# KONNEKTING_HW1_1_Rev1.net
KiCad netlist of a schematic drawn in EAGLE
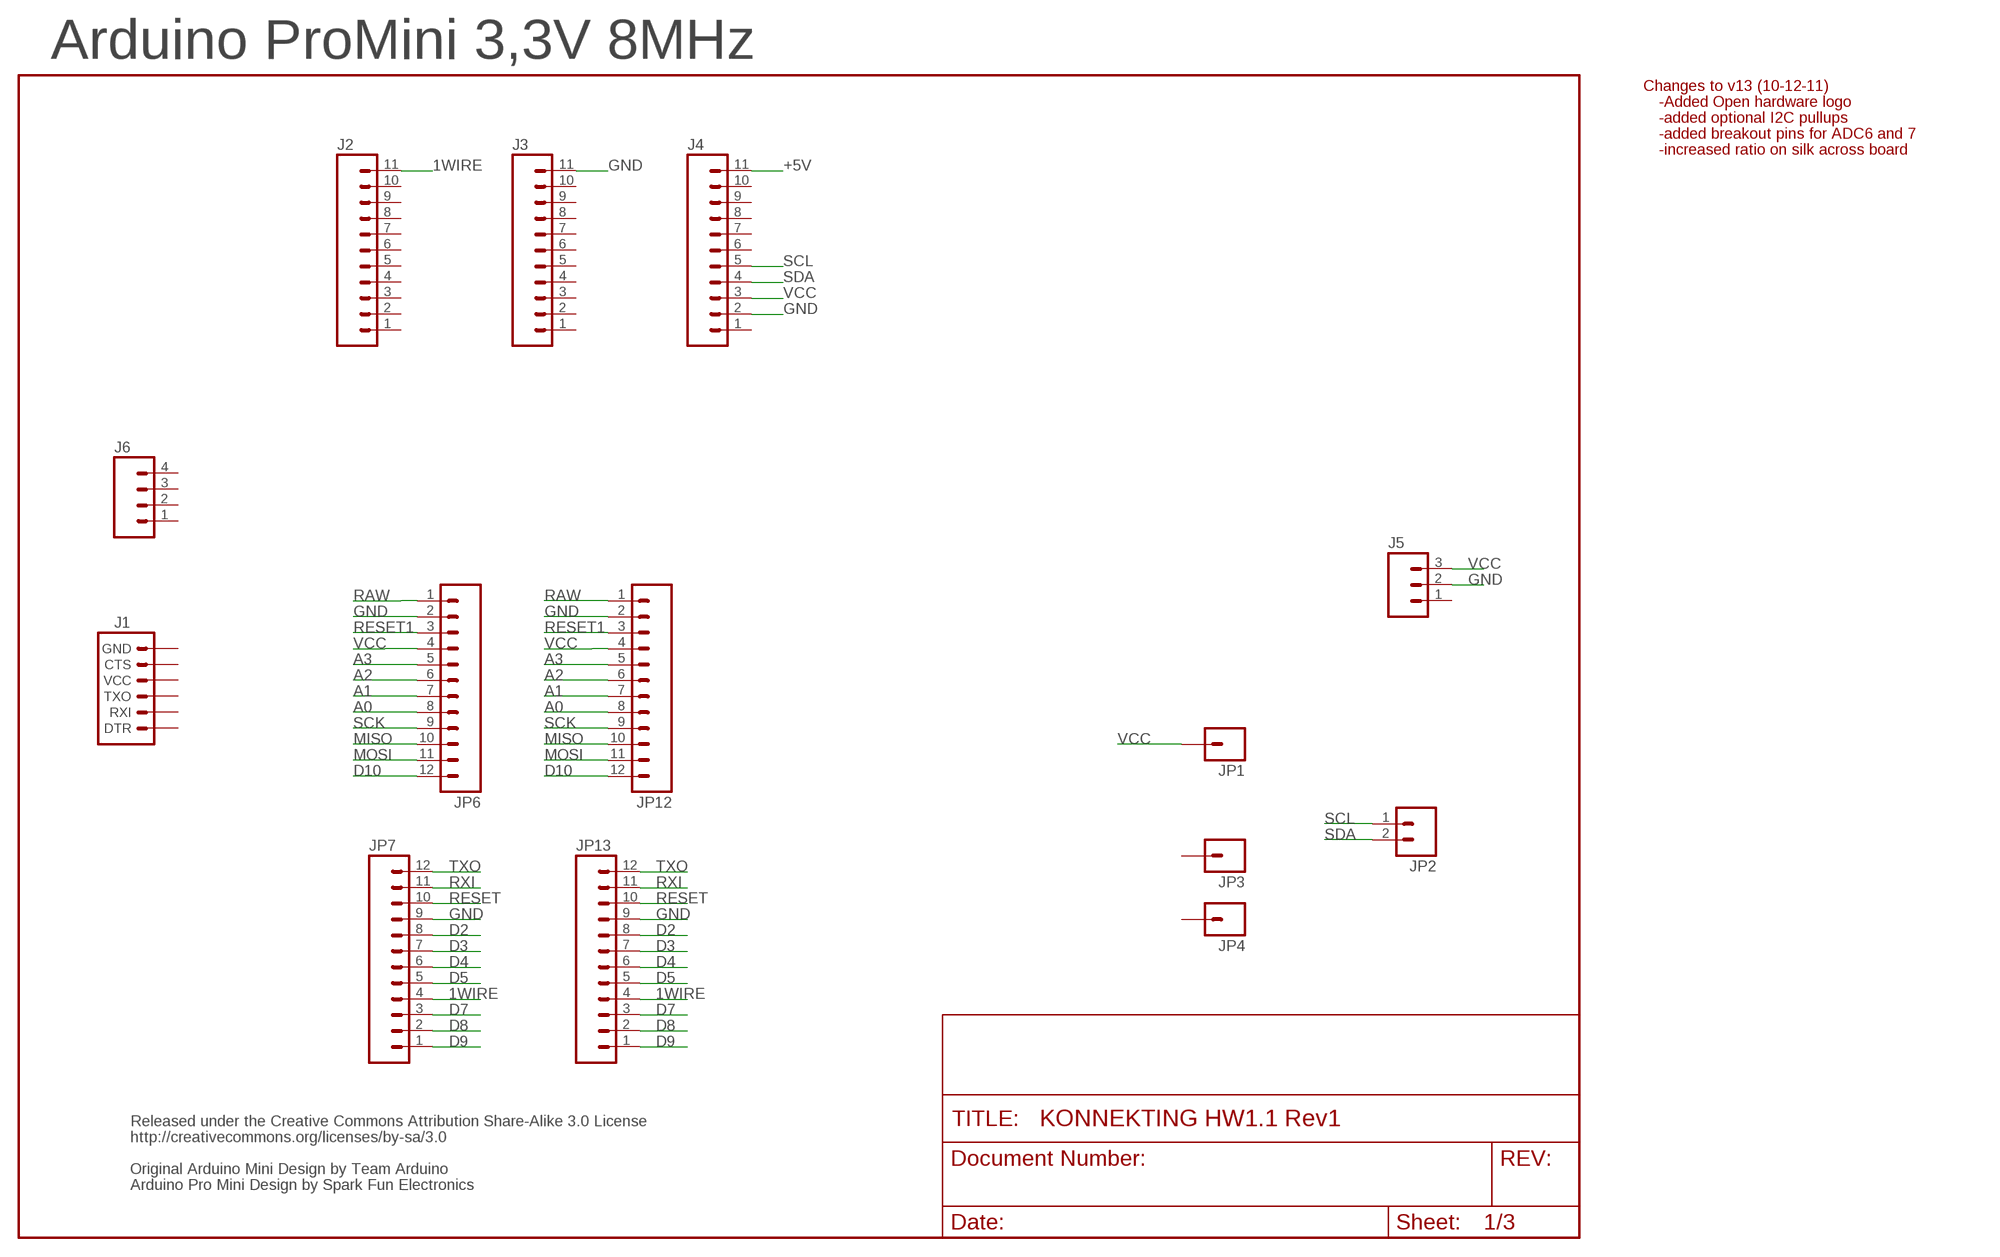
[diagram p0: schematic, sheet 1]
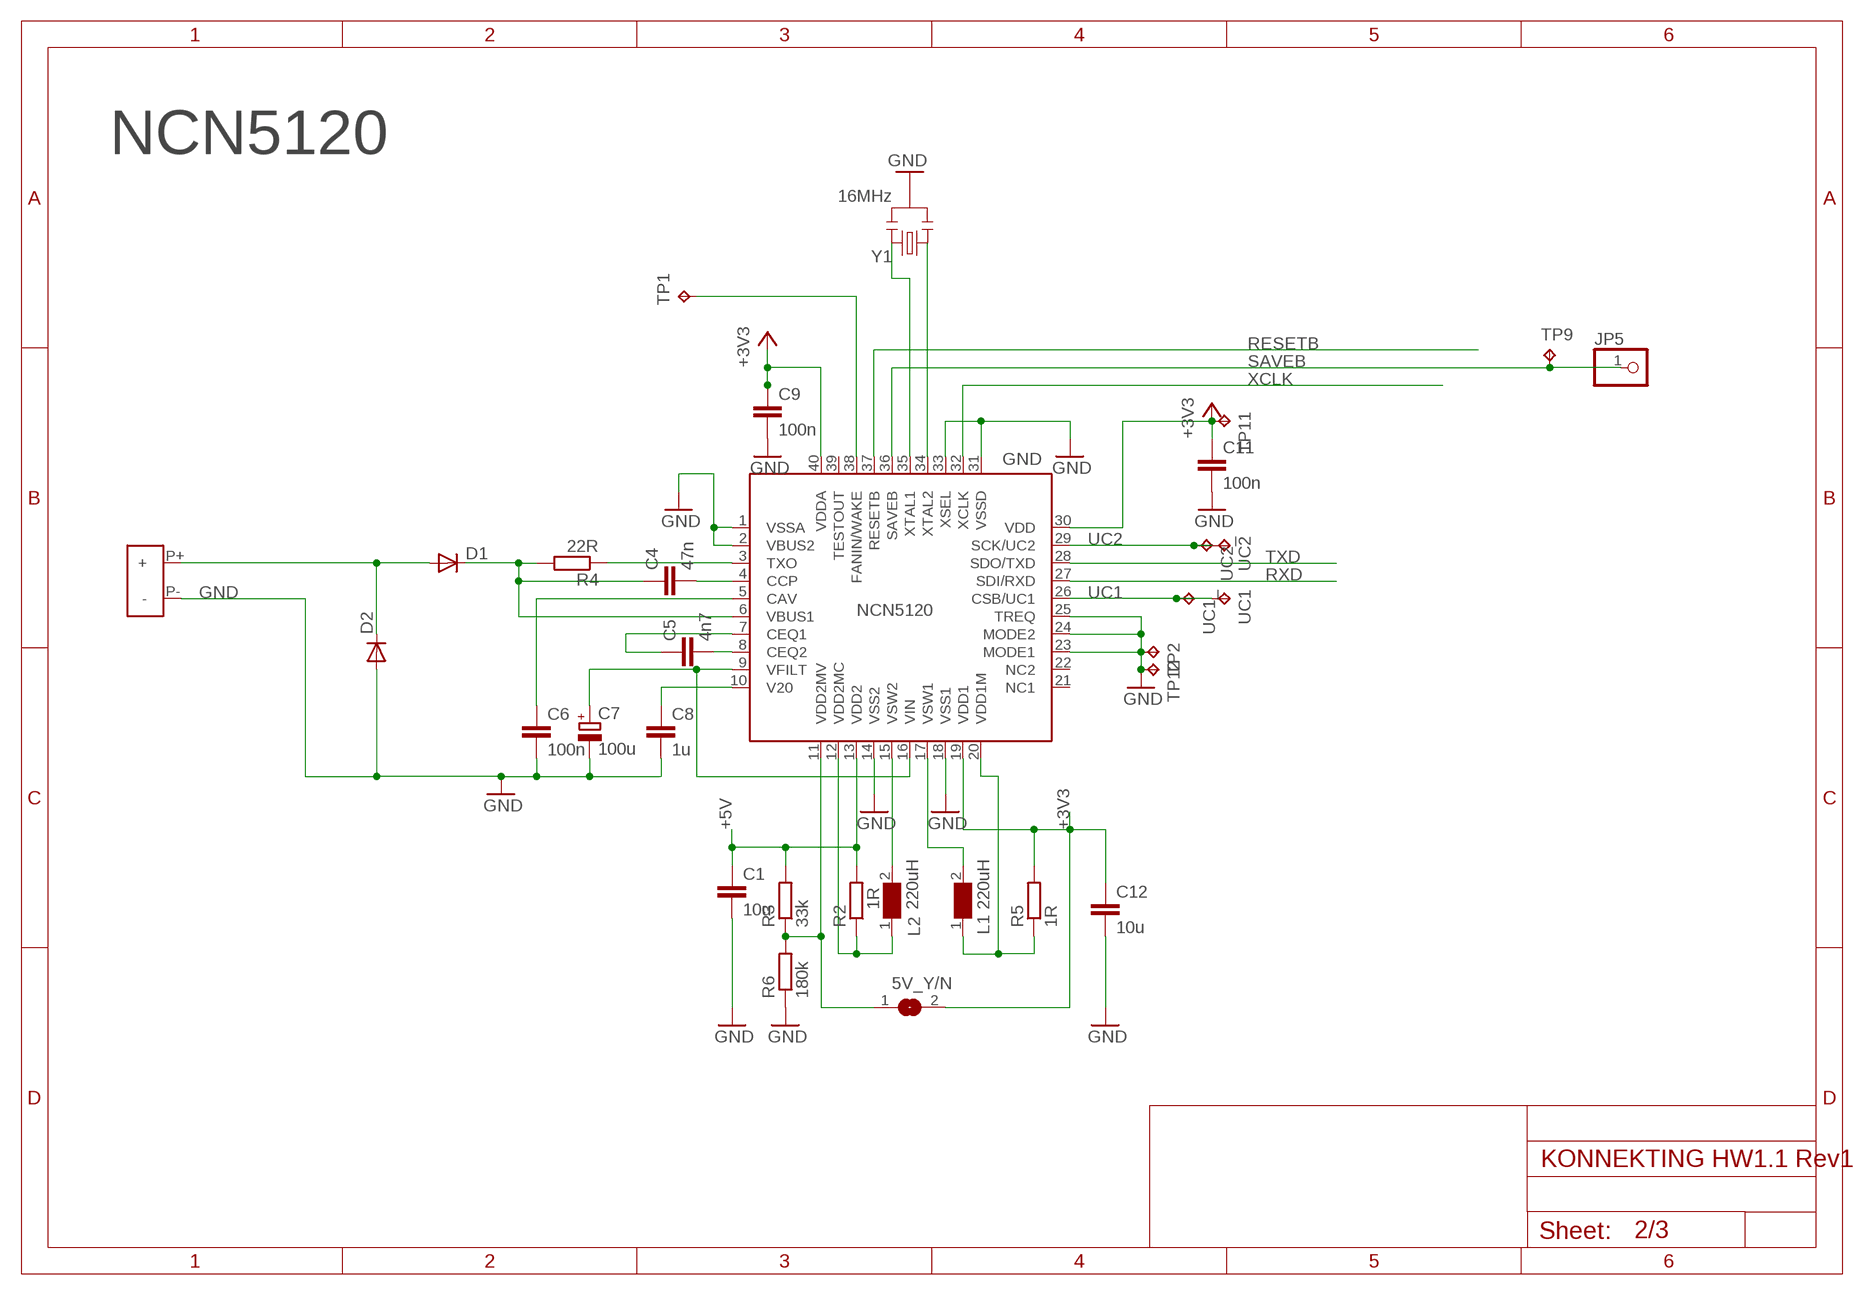
[diagram p1: schematic, sheet 2]
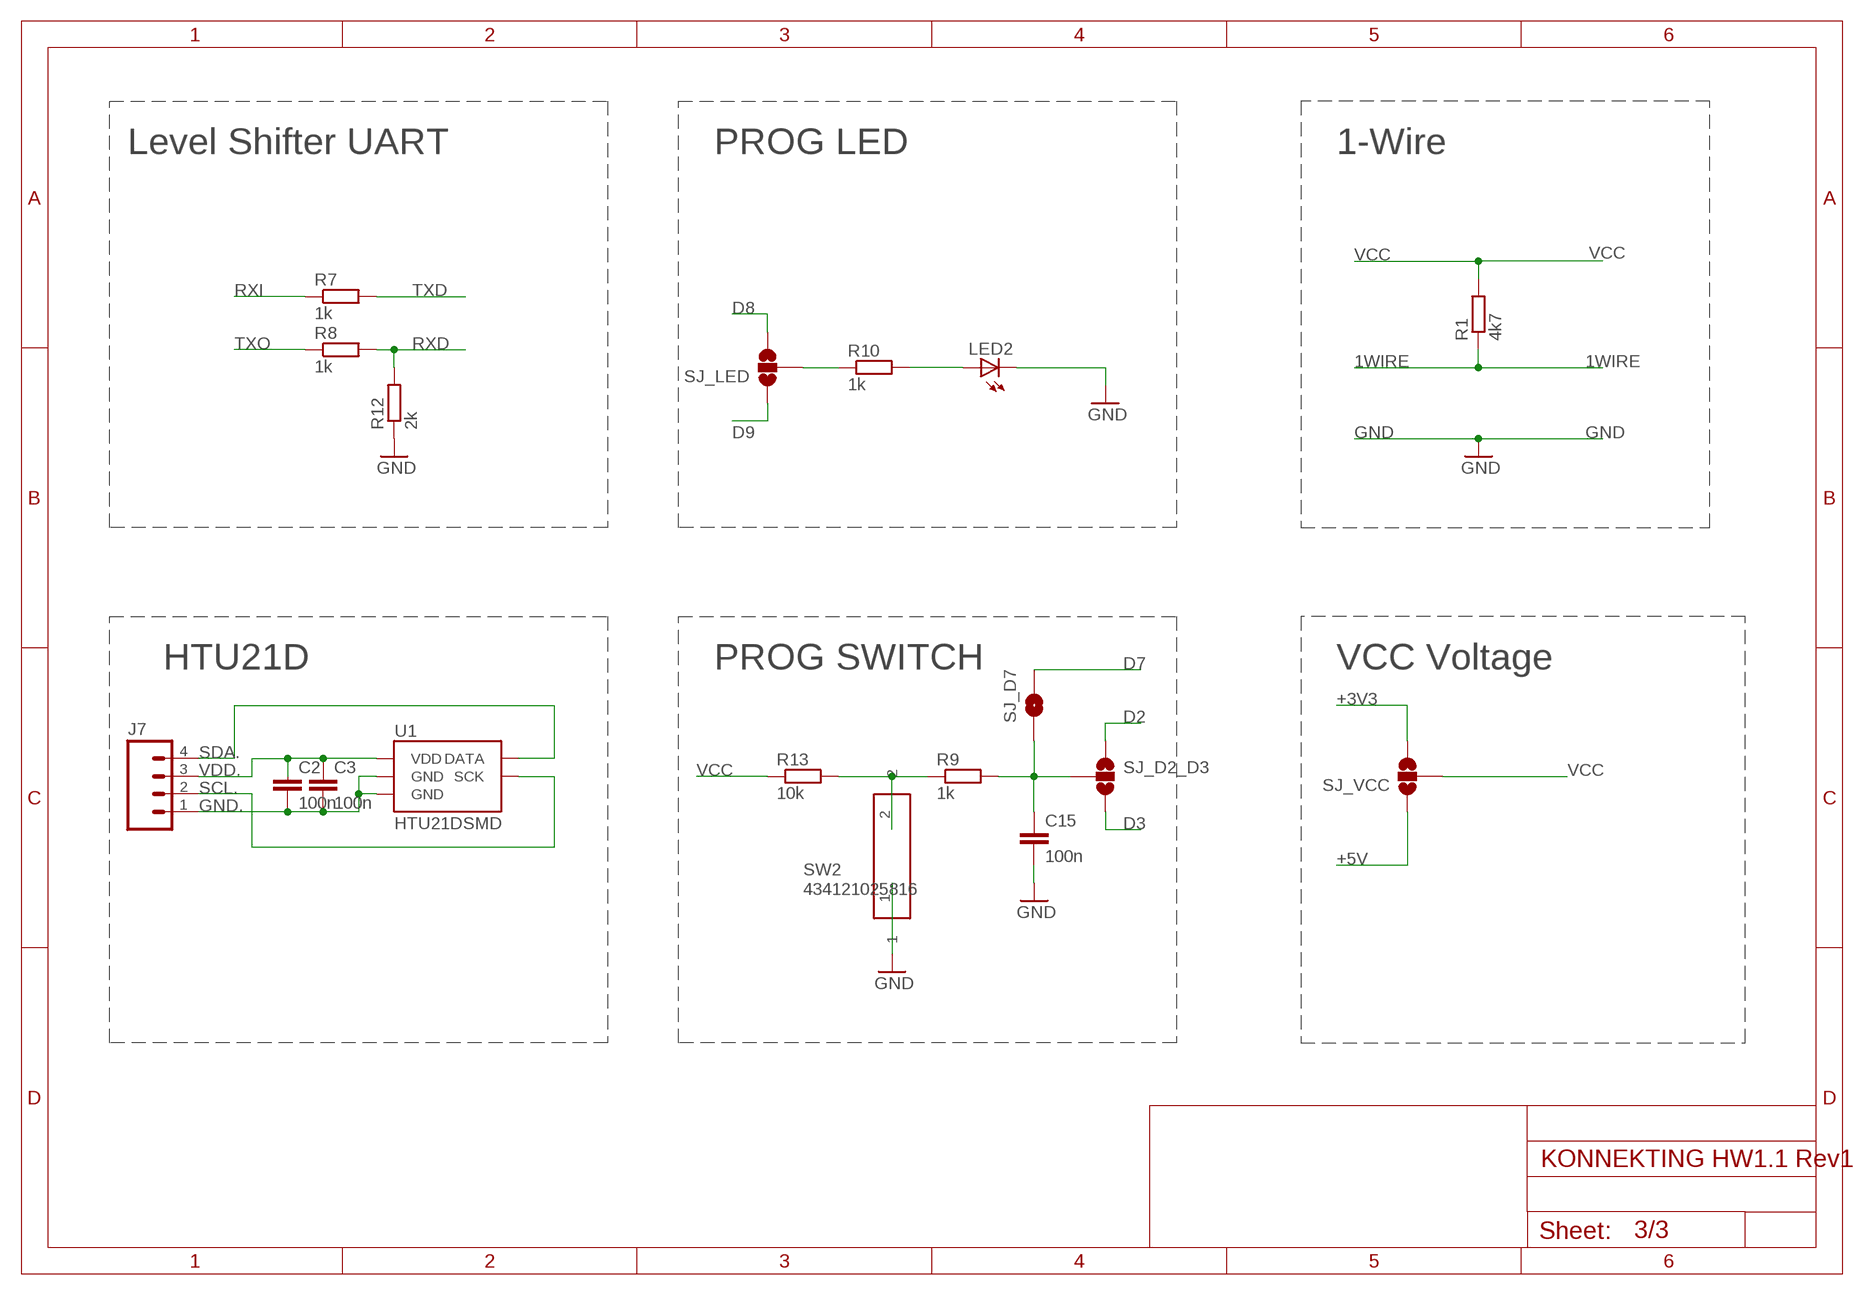
[diagram p2: schematic, sheet 3]

(export (version "E")
  (design (tool "Eeschema 10.0.6"))
  (components
    (comp (ref "J1")
      (value "ARDUINO_SERIAL_PROGRAMPTH")
      (footprint "eagle-import:1X06")
      (libsource (lib "eagle-import") (part "ARDUINO_SERIAL_PROGRAMPTH"))
    )
    (comp (ref "J2")
      (value "M11PTH")
      (footprint "eagle-import:1X11")
      (libsource (lib "eagle-import") (part "M11PTH"))
    )
    (comp (ref "J3")
      (value "M11PTH")
      (footprint "eagle-import:1X11")
      (libsource (lib "eagle-import") (part "M11PTH"))
    )
    (comp (ref "J4")
      (value "M11PTH")
      (footprint "eagle-import:1X11")
      (libsource (lib "eagle-import") (part "M11PTH"))
    )
    (comp (ref "J5")
      (value "M03PTH")
      (footprint "eagle-import:1X03")
      (libsource (lib "eagle-import") (part "M03PTH"))
    )
    (comp (ref "J6")
      (value "M04PTH")
      (footprint "eagle-import:1X04")
      (libsource (lib "eagle-import") (part "M04PTH"))
    )
    (comp (ref "JP1")
      (value "M01PTH")
      (footprint "eagle-import:1X01")
      (libsource (lib "eagle-import") (part "M01PTH"))
    )
    (comp (ref "JP2")
      (value "M02PTH")
      (footprint "eagle-import:1X02")
      (libsource (lib "eagle-import") (part "M02PTH"))
    )
    (comp (ref "JP3")
      (value "M01PTH")
      (footprint "eagle-import:1X01")
      (libsource (lib "eagle-import") (part "M01PTH"))
    )
    (comp (ref "JP4")
      (value "M01PTH")
      (footprint "eagle-import:1X01")
      (libsource (lib "eagle-import") (part "M01PTH"))
    )
    (comp (ref "JP6")
      (value "M12PTH")
      (footprint "eagle-import:1X12")
      (libsource (lib "eagle-import") (part "M12PTH"))
    )
    (comp (ref "JP7")
      (value "M12PTH")
      (footprint "eagle-import:1X12")
      (libsource (lib "eagle-import") (part "M12PTH"))
    )
    (comp (ref "JP12")
      (value "M12PTH")
      (footprint "eagle-import:1X12")
      (libsource (lib "eagle-import") (part "M12PTH"))
    )
    (comp (ref "JP13")
      (value "M12PTH")
      (footprint "eagle-import:1X12")
      (libsource (lib "eagle-import") (part "M12PTH"))
    )
    (comp (ref "5V_Y/N")
      (value "SJ")
      (footprint "eagle-import:SJ")
      (libsource (lib "eagle-import") (part "SJ"))
    )
    (comp (ref "C1")
      (value "10u")
      (footprint "eagle-import:C0805")
      (libsource (lib "eagle-import") (part "C-EUC0805"))
    )
    (comp (ref "C4")
      (value "47n")
      (footprint "eagle-import:C0603")
      (libsource (lib "eagle-import") (part "C-EUC0603"))
    )
    (comp (ref "C5")
      (value "4n7")
      (footprint "eagle-import:C0603")
      (libsource (lib "eagle-import") (part "C-EUC0603"))
    )
    (comp (ref "C6")
      (value "100n")
      (footprint "eagle-import:C0603")
      (libsource (lib "eagle-import") (part "C-EUC0603"))
    )
    (comp (ref "C7")
      (value "100u")
      (footprint "eagle-import:UD-6,3X7,7_NICHICON")
      (libsource (lib "eagle-import") (part "CPOL-EUUD-6,3X7,7"))
    )
    (comp (ref "C8")
      (value "1u")
      (footprint "eagle-import:C0603")
      (libsource (lib "eagle-import") (part "C-EUC0603"))
    )
    (comp (ref "C9")
      (value "100n")
      (footprint "eagle-import:C0603")
      (libsource (lib "eagle-import") (part "C-EUC0603"))
    )
    (comp (ref "C11")
      (value "100n")
      (footprint "eagle-import:C0603")
      (libsource (lib "eagle-import") (part "C-EUC0603"))
    )
    (comp (ref "C12")
      (value "10u")
      (footprint "eagle-import:C0805")
      (libsource (lib "eagle-import") (part "C-EUC0805"))
    )
    (comp (ref "D1")
      (value "DIODESMA-ALT")
      (footprint "eagle-import:SMA-DIODE_ALT")
      (libsource (lib "eagle-import") (part "DIODESMA-ALT"))
    )
    (comp (ref "D2")
      (value "DIODESMA-ALT")
      (footprint "eagle-import:SMA-DIODE_ALT")
      (libsource (lib "eagle-import") (part "DIODESMA-ALT"))
    )
    (comp (ref "GND")
      (value "NCN5120_KNX_TRANSCEIVER")
      (footprint "eagle-import:QFN40")
      (libsource (lib "eagle-import") (part "NCN5120_KNX_TRANSCEIVER"))
    )
    (comp (ref "JP5")
      (value "PINHD-1X1")
      (footprint "eagle-import:1X01")
      (libsource (lib "eagle-import") (part "PINHD-1X1"))
    )
    (comp (ref "L1")
      (value "220uH")
      (footprint "eagle-import:WE-PD2_7850")
      (libsource (lib "eagle-import") (part "WE-PD2_7850"))
    )
    (comp (ref "L2")
      (value "220uH")
      (footprint "eagle-import:WE-PD2_7850")
      (libsource (lib "eagle-import") (part "WE-PD2_7850"))
    )
    (comp (ref "R2")
      (value "1R")
      (footprint "eagle-import:R0603")
      (libsource (lib "eagle-import") (part "R-EU_R0603"))
    )
    (comp (ref "R3")
      (value "33k")
      (footprint "eagle-import:R0603")
      (libsource (lib "eagle-import") (part "R-EU_R0603"))
    )
    (comp (ref "R4")
      (value "22R")
      (footprint "eagle-import:R2512")
      (libsource (lib "eagle-import") (part "R-EU_R2512"))
    )
    (comp (ref "R5")
      (value "1R")
      (footprint "eagle-import:R0603")
      (libsource (lib "eagle-import") (part "R-EU_R0603"))
    )
    (comp (ref "R6")
      (value "180k")
      (footprint "eagle-import:R0603")
      (libsource (lib "eagle-import") (part "R-EU_R0603"))
    )
    (comp (ref "TP1")
      (value "TPTP10SQ")
      (footprint "eagle-import:TP10SQ")
      (libsource (lib "eagle-import") (part "TPTP10SQ"))
    )
    (comp (ref "TP2")
      (value "TPTP09SQ")
      (footprint "eagle-import:TP09SQ")
      (libsource (lib "eagle-import") (part "TPTP09SQ"))
    )
    (comp (ref "TP9")
      (value "TPTP10SQ")
      (footprint "eagle-import:TP10SQ")
      (libsource (lib "eagle-import") (part "TPTP10SQ"))
    )
    (comp (ref "TP11")
      (value "TPTP09SQ")
      (footprint "eagle-import:TP09SQ")
      (libsource (lib "eagle-import") (part "TPTP09SQ"))
    )
    (comp (ref "TP12")
      (value "TPTP09SQ")
      (footprint "eagle-import:TP09SQ")
      (libsource (lib "eagle-import") (part "TPTP09SQ"))
    )
    (comp (ref "U$2")
      (value "KNX_KLEMME")
      (footprint "eagle-import:KNX_KLEMME")
      (libsource (lib "eagle-import") (part "KNX_KLEMME"))
    )
    (comp (ref "UC1")
      (value "TPTP09SQ")
      (footprint "eagle-import:TP09SQ")
      (libsource (lib "eagle-import") (part "TPTP09SQ"))
    )
    (comp (ref "UC1_")
      (value "TPTP09SQ")
      (footprint "eagle-import:TP09SQ")
      (libsource (lib "eagle-import") (part "TPTP09SQ"))
    )
    (comp (ref "UC2")
      (value "TPTP09SQ")
      (footprint "eagle-import:TP09SQ")
      (libsource (lib "eagle-import") (part "TPTP09SQ"))
    )
    (comp (ref "UC2_")
      (value "TPTP09SQ")
      (footprint "eagle-import:TP09SQ")
      (libsource (lib "eagle-import") (part "TPTP09SQ"))
    )
    (comp (ref "Y1")
      (value "16MHz")
      (footprint "eagle-import:RESONATOR-SMD")
      (libsource (lib "eagle-import") (part "RESONATORSMD"))
    )
    (comp (ref "C2")
      (value "100n")
      (footprint "eagle-import:0603-CAP")
      (libsource (lib "eagle-import") (part "CAP0603-CAP"))
    )
    (comp (ref "C3")
      (value "100n")
      (footprint "eagle-import:0603-CAP")
      (libsource (lib "eagle-import") (part "CAP0603-CAP"))
    )
    (comp (ref "C15")
      (value "100n")
      (footprint "eagle-import:C0603")
      (libsource (lib "eagle-import") (part "C-EUC0603"))
    )
    (comp (ref "J7")
      (value "M04PTH")
      (footprint "eagle-import:1X04")
      (libsource (lib "eagle-import") (part "M04PTH"))
    )
    (comp (ref "LED2")
      (value "LEDCHIP-LED0805")
      (footprint "eagle-import:CHIP-LED0805")
      (libsource (lib "eagle-import") (part "LEDCHIP-LED0805"))
    )
    (comp (ref "R1")
      (value "4k7")
      (footprint "eagle-import:R0603")
      (libsource (lib "eagle-import") (part "R-EU_R0603"))
    )
    (comp (ref "R7")
      (value "1k")
      (footprint "eagle-import:R0805")
      (libsource (lib "eagle-import") (part "R-EU_R0805"))
    )
    (comp (ref "R8")
      (value "1k")
      (footprint "eagle-import:R0805")
      (libsource (lib "eagle-import") (part "R-EU_R0805"))
    )
    (comp (ref "R9")
      (value "1k")
      (footprint "eagle-import:R0603")
      (libsource (lib "eagle-import") (part "R-EU_R0603"))
    )
    (comp (ref "R10")
      (value "1k")
      (footprint "eagle-import:R0603")
      (libsource (lib "eagle-import") (part "R-EU_R0603"))
    )
    (comp (ref "R12")
      (value "2k")
      (footprint "eagle-import:R0805")
      (libsource (lib "eagle-import") (part "R-EU_R0805"))
    )
    (comp (ref "R13")
      (value "10k")
      (footprint "eagle-import:R0603")
      (libsource (lib "eagle-import") (part "R-EU_R0603"))
    )
    (comp (ref "SJ_D2_D3")
      (value "SOLDERJUMPER_2WAYS")
      (footprint "eagle-import:SJ_3")
      (libsource (lib "eagle-import") (part "SOLDERJUMPER_2WAYS"))
    )
    (comp (ref "SJ_D7")
      (value "SOLDERJUMPERNO")
      (footprint "eagle-import:SJ_2S-NO")
      (libsource (lib "eagle-import") (part "SOLDERJUMPERNO"))
    )
    (comp (ref "SJ_LED")
      (value "SOLDERJUMPER_2WAYS")
      (footprint "eagle-import:SJ_3")
      (libsource (lib "eagle-import") (part "SOLDERJUMPER_2WAYS"))
    )
    (comp (ref "SJ_VCC")
      (value "SOLDERJUMPER_2WAYS")
      (footprint "eagle-import:SJ_3")
      (libsource (lib "eagle-import") (part "SOLDERJUMPER_2WAYS"))
    )
    (comp (ref "SW2")
      (value "434121025816")
      (footprint "eagle-import:434121025816")
      (libsource (lib "eagle-import") (part "434121025816"))
    )
    (comp (ref "U1")
      (value "HTU21DSMD")
      (footprint "eagle-import:HTU21D")
      (libsource (lib "eagle-import") (part "HTU21DSMD"))
    )
  )
  (nets
    (net (code "1") (name "+3V3") (class "Default")
      (node (ref "5V_Y/N") (pin "2") (pinfunction "2_2") (pintype "passive"))
      (node (ref "C11") (pin "1") (pinfunction "1_1") (pintype "passive"))
      (node (ref "C12") (pin "1") (pinfunction "1_1") (pintype "passive"))
      (node (ref "C9") (pin "1") (pinfunction "1_1") (pintype "passive"))
      (node (ref "GND") (pin "19") (pinfunction "VDD1_19") (pintype "bidirectional"))
      (node (ref "GND") (pin "30") (pinfunction "VDD_30") (pintype "bidirectional"))
      (node (ref "GND") (pin "40") (pinfunction "VDDA_40") (pintype "bidirectional"))
      (node (ref "R5") (pin "2") (pinfunction "2_2") (pintype "passive"))
      (node (ref "SJ_VCC") (pin "3") (pinfunction "3_3") (pintype "passive"))
      (node (ref "TP11") (pin "TP") (pinfunction "TP_TP") (pintype "input"))
    )
    (net (code "2") (name "+5V") (class "Default")
      (node (ref "C1") (pin "1") (pinfunction "1_1") (pintype "passive"))
      (node (ref "GND") (pin "13") (pinfunction "VDD2_13") (pintype "bidirectional"))
      (node (ref "J4") (pin "11") (pinfunction "11_11") (pintype "passive"))
      (node (ref "R2") (pin "2") (pinfunction "2_2") (pintype "passive"))
      (node (ref "R3") (pin "2") (pinfunction "2_2") (pintype "passive"))
      (node (ref "SJ_VCC") (pin "1") (pinfunction "1_1") (pintype "passive"))
    )
    (net (code "3") (name "1WIRE") (class "Default")
      (node (ref "J2") (pin "11") (pinfunction "11_11") (pintype "passive"))
      (node (ref "JP13") (pin "4") (pinfunction "4_4") (pintype "passive"))
      (node (ref "JP7") (pin "4") (pinfunction "4_4") (pintype "passive"))
      (node (ref "R1") (pin "1") (pinfunction "1_1") (pintype "passive"))
    )
    (net (code "4") (name "A0") (class "Default")
      (node (ref "JP12") (pin "8") (pinfunction "8_8") (pintype "passive"))
      (node (ref "JP6") (pin "8") (pinfunction "8_8") (pintype "passive"))
    )
    (net (code "5") (name "A1") (class "Default")
      (node (ref "JP12") (pin "7") (pinfunction "7_7") (pintype "passive"))
      (node (ref "JP6") (pin "7") (pinfunction "7_7") (pintype "passive"))
    )
    (net (code "6") (name "A2") (class "Default")
      (node (ref "JP12") (pin "6") (pinfunction "6_6") (pintype "passive"))
      (node (ref "JP6") (pin "6") (pinfunction "6_6") (pintype "passive"))
    )
    (net (code "7") (name "A3") (class "Default")
      (node (ref "JP12") (pin "5") (pinfunction "5_5") (pintype "passive"))
      (node (ref "JP6") (pin "5") (pinfunction "5_5") (pintype "passive"))
    )
    (net (code "8") (name "D2") (class "Default")
      (node (ref "JP13") (pin "8") (pinfunction "8_8") (pintype "passive"))
      (node (ref "JP7") (pin "8") (pinfunction "8_8") (pintype "passive"))
      (node (ref "SJ_D2_D3") (pin "1") (pinfunction "1_1") (pintype "passive"))
    )
    (net (code "9") (name "D3") (class "Default")
      (node (ref "JP13") (pin "7") (pinfunction "7_7") (pintype "passive"))
      (node (ref "JP7") (pin "7") (pinfunction "7_7") (pintype "passive"))
      (node (ref "SJ_D2_D3") (pin "3") (pinfunction "3_3") (pintype "passive"))
    )
    (net (code "10") (name "D4") (class "Default")
      (node (ref "JP13") (pin "6") (pinfunction "6_6") (pintype "passive"))
      (node (ref "JP7") (pin "6") (pinfunction "6_6") (pintype "passive"))
    )
    (net (code "11") (name "D5") (class "Default")
      (node (ref "JP13") (pin "5") (pinfunction "5_5") (pintype "passive"))
      (node (ref "JP7") (pin "5") (pinfunction "5_5") (pintype "passive"))
    )
    (net (code "12") (name "D7") (class "Default")
      (node (ref "JP13") (pin "3") (pinfunction "3_3") (pintype "passive"))
      (node (ref "JP7") (pin "3") (pinfunction "3_3") (pintype "passive"))
      (node (ref "SJ_D7") (pin "2") (pinfunction "2_2") (pintype "passive"))
    )
    (net (code "13") (name "D8") (class "Default")
      (node (ref "JP13") (pin "2") (pinfunction "2_2") (pintype "passive"))
      (node (ref "JP7") (pin "2") (pinfunction "2_2") (pintype "passive"))
      (node (ref "SJ_LED") (pin "3") (pinfunction "3_3") (pintype "passive"))
    )
    (net (code "14") (name "D9") (class "Default")
      (node (ref "JP13") (pin "1") (pinfunction "1_1") (pintype "passive"))
      (node (ref "JP7") (pin "1") (pinfunction "1_1") (pintype "passive"))
      (node (ref "SJ_LED") (pin "1") (pinfunction "1_1") (pintype "passive"))
    )
    (net (code "15") (name "D10") (class "Default")
      (node (ref "JP12") (pin "12") (pinfunction "12_12") (pintype "passive"))
      (node (ref "JP6") (pin "12") (pinfunction "12_12") (pintype "passive"))
    )
    (net (code "16") (name "GND") (class "Default")
      (node (ref "C1") (pin "2") (pinfunction "2_2") (pintype "passive"))
      (node (ref "C11") (pin "2") (pinfunction "2_2") (pintype "passive"))
      (node (ref "C12") (pin "2") (pinfunction "2_2") (pintype "passive"))
      (node (ref "C15") (pin "2") (pinfunction "2_2") (pintype "passive"))
      (node (ref "C6") (pin "2") (pinfunction "2_2") (pintype "passive"))
      (node (ref "C7") (pin "-") (pinfunction "-_-") (pintype "passive"))
      (node (ref "C8") (pin "2") (pinfunction "2_2") (pintype "passive"))
      (node (ref "C9") (pin "2") (pinfunction "2_2") (pintype "passive"))
      (node (ref "D2") (pin "A") (pinfunction "A_A") (pintype "passive"))
      (node (ref "GND") (pin "1") (pinfunction "VSSA_1") (pintype "bidirectional"))
      (node (ref "GND") (pin "14") (pinfunction "VSS2_14") (pintype "bidirectional"))
      (node (ref "GND") (pin "18") (pinfunction "VSS1_18") (pintype "bidirectional"))
      (node (ref "GND") (pin "2") (pinfunction "VBUS2_2") (pintype "bidirectional"))
      (node (ref "GND") (pin "23") (pinfunction "MODE1_23") (pintype "bidirectional"))
      (node (ref "GND") (pin "24") (pinfunction "MODE2_24") (pintype "bidirectional"))
      (node (ref "GND") (pin "25") (pinfunction "TREQ_25") (pintype "bidirectional"))
      (node (ref "GND") (pin "31") (pinfunction "VSSD_31") (pintype "bidirectional"))
      (node (ref "GND") (pin "33") (pinfunction "XSEL_33") (pintype "bidirectional"))
      (node (ref "J3") (pin "11") (pinfunction "11_11") (pintype "passive"))
      (node (ref "J4") (pin "2") (pinfunction "2_2") (pintype "passive"))
      (node (ref "J5") (pin "2") (pinfunction "2_2") (pintype "passive"))
      (node (ref "JP12") (pin "2") (pinfunction "2_2") (pintype "passive"))
      (node (ref "JP13") (pin "9") (pinfunction "9_9") (pintype "passive"))
      (node (ref "JP6") (pin "2") (pinfunction "2_2") (pintype "passive"))
      (node (ref "JP7") (pin "9") (pinfunction "9_9") (pintype "passive"))
      (node (ref "LED2") (pin "C") (pinfunction "C_C") (pintype "passive"))
      (node (ref "R12") (pin "1") (pinfunction "1_1") (pintype "passive"))
      (node (ref "R6") (pin "1") (pinfunction "1_1") (pintype "passive"))
      (node (ref "SW2") (pin "1") (pinfunction "1_1") (pintype "bidirectional"))
      (node (ref "TP12") (pin "TP") (pinfunction "TP_TP") (pintype "input"))
      (node (ref "TP2") (pin "TP") (pinfunction "TP_TP") (pintype "input"))
      (node (ref "U$2") (pin "P-") (pinfunction "-_P-") (pintype "bidirectional"))
      (node (ref "Y1") (pin "2") (pinfunction "2_2") (pintype "passive"))
    )
    (net (code "17") (name "GND.") (class "Default")
      (node (ref "C2") (pin "2") (pinfunction "2_2") (pintype "passive"))
      (node (ref "C3") (pin "2") (pinfunction "2_2") (pintype "passive"))
      (node (ref "J7") (pin "1") (pinfunction "1_1") (pintype "passive"))
      (node (ref "U1") (pin "7") (pinfunction "GND_7") (pintype "power_in"))
      (node (ref "U1") (pin "GND") (pinfunction "GND_GND") (pintype "power_in"))
    )
    (net (code "18") (name "MISO") (class "Default")
      (node (ref "JP12") (pin "10") (pinfunction "10_10") (pintype "passive"))
      (node (ref "JP6") (pin "10") (pinfunction "10_10") (pintype "passive"))
    )
    (net (code "19") (name "MOSI") (class "Default")
      (node (ref "JP12") (pin "11") (pinfunction "11_11") (pintype "passive"))
      (node (ref "JP6") (pin "11") (pinfunction "11_11") (pintype "passive"))
    )
    (net (code "20") (name "Net-(C15-Pad1)") (class "Default")
      (node (ref "C15") (pin "1") (pinfunction "1_1") (pintype "passive"))
      (node (ref "R9") (pin "2") (pinfunction "2_2") (pintype "passive"))
      (node (ref "SJ_D2_D3") (pin "2") (pinfunction "2_2") (pintype "passive"))
      (node (ref "SJ_D7") (pin "1") (pinfunction "1_1") (pintype "passive"))
    )
    (net (code "21") (name "Net-(GND-CAV)") (class "Default")
      (node (ref "C6") (pin "1") (pinfunction "1_1") (pintype "passive"))
      (node (ref "GND") (pin "5") (pinfunction "CAV_5") (pintype "bidirectional"))
    )
    (net (code "22") (name "Net-(GND-CCP)") (class "Default")
      (node (ref "C4") (pin "2") (pinfunction "2_2") (pintype "passive"))
      (node (ref "GND") (pin "4") (pinfunction "CCP_4") (pintype "bidirectional"))
    )
    (net (code "23") (name "Net-(GND-CEQ1)") (class "Default")
      (node (ref "C5") (pin "1") (pinfunction "1_1") (pintype "passive"))
      (node (ref "GND") (pin "7") (pinfunction "CEQ1_7") (pintype "bidirectional"))
    )
    (net (code "24") (name "Net-(GND-CEQ2)") (class "Default")
      (node (ref "C5") (pin "2") (pinfunction "2_2") (pintype "passive"))
      (node (ref "GND") (pin "8") (pinfunction "CEQ2_8") (pintype "bidirectional"))
    )
    (net (code "25") (name "Net-(GND-FANIN{slash}WAKE)") (class "Default")
      (node (ref "GND") (pin "38") (pinfunction "FANIN/WAKE_38") (pintype "bidirectional"))
      (node (ref "TP1") (pin "TP") (pinfunction "TP_TP") (pintype "input"))
    )
    (net (code "26") (name "Net-(GND-TXO)") (class "Default")
      (node (ref "GND") (pin "3") (pinfunction "TXO_3") (pintype "bidirectional"))
      (node (ref "R4") (pin "1") (pinfunction "1_1") (pintype "passive"))
    )
    (net (code "27") (name "Net-(GND-V20)") (class "Default")
      (node (ref "C8") (pin "1") (pinfunction "1_1") (pintype "passive"))
      (node (ref "GND") (pin "10") (pinfunction "V20_10") (pintype "bidirectional"))
    )
    (net (code "28") (name "Net-(GND-VBUS1)") (class "Default")
      (node (ref "C4") (pin "1") (pinfunction "1_1") (pintype "passive"))
      (node (ref "D1") (pin "C") (pinfunction "C_C") (pintype "passive"))
      (node (ref "GND") (pin "6") (pinfunction "VBUS1_6") (pintype "bidirectional"))
      (node (ref "R4") (pin "2") (pinfunction "2_2") (pintype "passive"))
    )
    (net (code "29") (name "Net-(GND-VDD1M)") (class "Default")
      (node (ref "GND") (pin "20") (pinfunction "VDD1M_20") (pintype "bidirectional"))
      (node (ref "L1") (pin "1") (pinfunction "1_1") (pintype "passive"))
      (node (ref "R5") (pin "1") (pinfunction "1_1") (pintype "passive"))
    )
    (net (code "30") (name "Net-(GND-VDD2MC)") (class "Default")
      (node (ref "GND") (pin "12") (pinfunction "VDD2MC_12") (pintype "bidirectional"))
      (node (ref "L2") (pin "1") (pinfunction "1_1") (pintype "passive"))
      (node (ref "R2") (pin "1") (pinfunction "1_1") (pintype "passive"))
    )
    (net (code "31") (name "Net-(GND-VDD2MV)") (class "Default")
      (node (ref "5V_Y/N") (pin "1") (pinfunction "1_1") (pintype "passive"))
      (node (ref "GND") (pin "11") (pinfunction "VDD2MV_11") (pintype "bidirectional"))
      (node (ref "R3") (pin "1") (pinfunction "1_1") (pintype "passive"))
      (node (ref "R6") (pin "2") (pinfunction "2_2") (pintype "passive"))
    )
    (net (code "32") (name "Net-(GND-VFILT)") (class "Default")
      (node (ref "C7") (pin "+") (pinfunction "+_+") (pintype "passive"))
      (node (ref "GND") (pin "16") (pinfunction "VIN_16") (pintype "bidirectional"))
      (node (ref "GND") (pin "9") (pinfunction "VFILT_9") (pintype "bidirectional"))
    )
    (net (code "33") (name "Net-(GND-VSW1)") (class "Default")
      (node (ref "GND") (pin "17") (pinfunction "VSW1_17") (pintype "bidirectional"))
      (node (ref "L1") (pin "2") (pinfunction "2_2") (pintype "passive"))
    )
    (net (code "34") (name "Net-(GND-VSW2)") (class "Default")
      (node (ref "GND") (pin "15") (pinfunction "VSW2_15") (pintype "bidirectional"))
      (node (ref "L2") (pin "2") (pinfunction "2_2") (pintype "passive"))
    )
    (net (code "35") (name "Net-(GND-XTAL1)") (class "Default")
      (node (ref "GND") (pin "35") (pinfunction "XTAL1_35") (pintype "bidirectional"))
      (node (ref "Y1") (pin "3") (pinfunction "3_3") (pintype "passive"))
    )
    (net (code "36") (name "Net-(GND-XTAL2)") (class "Default")
      (node (ref "GND") (pin "34") (pinfunction "XTAL2_34") (pintype "bidirectional"))
      (node (ref "Y1") (pin "1") (pinfunction "1_1") (pintype "passive"))
    )
    (net (code "37") (name "Net-(LED2-PadA)") (class "Default")
      (node (ref "LED2") (pin "A") (pinfunction "A_A") (pintype "passive"))
      (node (ref "R10") (pin "2") (pinfunction "2_2") (pintype "passive"))
    )
    (net (code "38") (name "Net-(R10-Pad1)") (class "Default")
      (node (ref "R10") (pin "1") (pinfunction "1_1") (pintype "passive"))
      (node (ref "SJ_LED") (pin "2") (pinfunction "2_2") (pintype "passive"))
    )
    (net (code "39") (name "Net-(R13-Pad2)") (class "Default")
      (node (ref "R13") (pin "2") (pinfunction "2_2") (pintype "passive"))
      (node (ref "R9") (pin "1") (pinfunction "1_1") (pintype "passive"))
      (node (ref "SW2") (pin "2") (pinfunction "2_2") (pintype "bidirectional"))
    )
    (net (code "40") (name "Net-(U$2-+)") (class "Default")
      (node (ref "D1") (pin "A") (pinfunction "A_A") (pintype "passive"))
      (node (ref "D2") (pin "C") (pinfunction "C_C") (pintype "passive"))
      (node (ref "U$2") (pin "P+") (pinfunction "+_P+") (pintype "bidirectional"))
    )
    (net (code "41") (name "RAW") (class "Default")
      (node (ref "JP12") (pin "1") (pinfunction "1_1") (pintype "passive"))
      (node (ref "JP6") (pin "1") (pinfunction "1_1") (pintype "passive"))
    )
    (net (code "42") (name "RESET") (class "Default")
      (node (ref "JP13") (pin "10") (pinfunction "10_10") (pintype "passive"))
      (node (ref "JP7") (pin "10") (pinfunction "10_10") (pintype "passive"))
    )
    (net (code "43") (name "RESET1") (class "Default")
      (node (ref "JP12") (pin "3") (pinfunction "3_3") (pintype "passive"))
      (node (ref "JP6") (pin "3") (pinfunction "3_3") (pintype "passive"))
    )
    (net (code "44") (name "RESETB") (class "Default")
      (node (ref "GND") (pin "37") (pinfunction "RESETB_37") (pintype "bidirectional"))
    )
    (net (code "45") (name "RXD") (class "Default")
      (node (ref "GND") (pin "27") (pinfunction "SDI/RXD_27") (pintype "bidirectional"))
      (node (ref "R12") (pin "2") (pinfunction "2_2") (pintype "passive"))
      (node (ref "R8") (pin "2") (pinfunction "2_2") (pintype "passive"))
    )
    (net (code "46") (name "RXI") (class "Default")
      (node (ref "JP13") (pin "11") (pinfunction "11_11") (pintype "passive"))
      (node (ref "JP7") (pin "11") (pinfunction "11_11") (pintype "passive"))
      (node (ref "R7") (pin "1") (pinfunction "1_1") (pintype "passive"))
    )
    (net (code "47") (name "SAVEB") (class "Default")
      (node (ref "GND") (pin "36") (pinfunction "SAVEB_36") (pintype "bidirectional"))
      (node (ref "JP5") (pin "1") (pinfunction "1_1") (pintype "passive"))
      (node (ref "TP9") (pin "TP") (pinfunction "TP_TP") (pintype "input"))
    )
    (net (code "48") (name "SCK") (class "Default")
      (node (ref "JP12") (pin "9") (pinfunction "9_9") (pintype "passive"))
      (node (ref "JP6") (pin "9") (pinfunction "9_9") (pintype "passive"))
    )
    (net (code "49") (name "SCL") (class "Default")
      (node (ref "J4") (pin "5") (pinfunction "5_5") (pintype "passive"))
      (node (ref "JP2") (pin "1") (pinfunction "1_1") (pintype "passive"))
    )
    (net (code "50") (name "SCL.") (class "Default")
      (node (ref "J7") (pin "2") (pinfunction "2_2") (pintype "passive"))
      (node (ref "U1") (pin "SCK") (pinfunction "SCK_SCK") (pintype "input"))
    )
    (net (code "51") (name "SDA") (class "Default")
      (node (ref "J4") (pin "4") (pinfunction "4_4") (pintype "passive"))
      (node (ref "JP2") (pin "2") (pinfunction "2_2") (pintype "passive"))
    )
    (net (code "52") (name "SDA.") (class "Default")
      (node (ref "J7") (pin "4") (pinfunction "4_4") (pintype "passive"))
      (node (ref "U1") (pin "DATA") (pinfunction "DATA_DATA") (pintype "bidirectional"))
    )
    (net (code "53") (name "TXD") (class "Default")
      (node (ref "GND") (pin "28") (pinfunction "SDO/TXD_28") (pintype "bidirectional"))
      (node (ref "R7") (pin "2") (pinfunction "2_2") (pintype "passive"))
    )
    (net (code "54") (name "TXO") (class "Default")
      (node (ref "JP13") (pin "12") (pinfunction "12_12") (pintype "passive"))
      (node (ref "JP7") (pin "12") (pinfunction "12_12") (pintype "passive"))
      (node (ref "R8") (pin "1") (pinfunction "1_1") (pintype "passive"))
    )
    (net (code "55") (name "UC1") (class "Default")
      (node (ref "GND") (pin "26") (pinfunction "CSB/UC1_26") (pintype "bidirectional"))
      (node (ref "UC1") (pin "TP") (pinfunction "TP_TP") (pintype "input"))
      (node (ref "UC1_") (pin "TP") (pinfunction "TP_TP") (pintype "input"))
    )
    (net (code "56") (name "UC2") (class "Default")
      (node (ref "GND") (pin "29") (pinfunction "SCK/UC2_29") (pintype "bidirectional"))
      (node (ref "UC2") (pin "TP") (pinfunction "TP_TP") (pintype "input"))
      (node (ref "UC2_") (pin "TP") (pinfunction "TP_TP") (pintype "input"))
    )
    (net (code "57") (name "VCC") (class "Default")
      (node (ref "J4") (pin "3") (pinfunction "3_3") (pintype "passive"))
      (node (ref "J5") (pin "3") (pinfunction "3_3") (pintype "passive"))
      (node (ref "JP1") (pin "1") (pinfunction "1_1") (pintype "passive"))
      (node (ref "JP12") (pin "4") (pinfunction "4_4") (pintype "passive"))
      (node (ref "JP6") (pin "4") (pinfunction "4_4") (pintype "passive"))
      (node (ref "R1") (pin "2") (pinfunction "2_2") (pintype "passive"))
      (node (ref "R13") (pin "1") (pinfunction "1_1") (pintype "passive"))
      (node (ref "SJ_VCC") (pin "2") (pinfunction "2_2") (pintype "passive"))
    )
    (net (code "58") (name "VDD.") (class "Default")
      (node (ref "C2") (pin "1") (pinfunction "1_1") (pintype "passive"))
      (node (ref "C3") (pin "1") (pinfunction "1_1") (pintype "passive"))
      (node (ref "J7") (pin "3") (pinfunction "3_3") (pintype "passive"))
      (node (ref "U1") (pin "VDD") (pinfunction "VDD_VDD") (pintype "power_in"))
    )
    (net (code "59") (name "XCLK") (class "Default")
      (node (ref "GND") (pin "32") (pinfunction "XCLK_32") (pintype "bidirectional"))
    )
    (net (code "60") (name "unconnected-(GND-NC1-Pad21)") (class "Default")
      (node (ref "GND") (pin "21") (pinfunction "NC1_21") (pintype "bidirectional"))
    )
    (net (code "61") (name "unconnected-(GND-NC2-Pad22)") (class "Default")
      (node (ref "GND") (pin "22") (pinfunction "NC2_22") (pintype "bidirectional"))
    )
    (net (code "62") (name "unconnected-(GND-TESTOUT-Pad39)") (class "Default")
      (node (ref "GND") (pin "39") (pinfunction "TESTOUT_39") (pintype "bidirectional"))
    )
    (net (code "63") (name "unconnected-(J1-CTS-Pad5)") (class "Default")
      (node (ref "J1") (pin "5") (pinfunction "CTS_5") (pintype "passive"))
    )
    (net (code "64") (name "unconnected-(J1-DTR-Pad1)") (class "Default")
      (node (ref "J1") (pin "1") (pinfunction "DTR_1") (pintype "passive"))
    )
    (net (code "65") (name "unconnected-(J1-GND-Pad6)") (class "Default")
      (node (ref "J1") (pin "6") (pinfunction "GND_6") (pintype "passive"))
    )
    (net (code "66") (name "unconnected-(J1-RXI-Pad2)") (class "Default")
      (node (ref "J1") (pin "2") (pinfunction "RXI_2") (pintype "passive"))
    )
    (net (code "67") (name "unconnected-(J1-TXO-Pad3)") (class "Default")
      (node (ref "J1") (pin "3") (pinfunction "TXO_3") (pintype "passive"))
    )
    (net (code "68") (name "unconnected-(J1-VCC-Pad4)") (class "Default")
      (node (ref "J1") (pin "4") (pinfunction "VCC_4") (pintype "passive"))
    )
    (net (code "69") (name "unconnected-(J2-Pad1)") (class "Default")
      (node (ref "J2") (pin "1") (pinfunction "1_1") (pintype "passive"))
    )
    (net (code "70") (name "unconnected-(J2-Pad2)") (class "Default")
      (node (ref "J2") (pin "2") (pinfunction "2_2") (pintype "passive"))
    )
    (net (code "71") (name "unconnected-(J2-Pad3)") (class "Default")
      (node (ref "J2") (pin "3") (pinfunction "3_3") (pintype "passive"))
    )
    (net (code "72") (name "unconnected-(J2-Pad4)") (class "Default")
      (node (ref "J2") (pin "4") (pinfunction "4_4") (pintype "passive"))
    )
    (net (code "73") (name "unconnected-(J2-Pad5)") (class "Default")
      (node (ref "J2") (pin "5") (pinfunction "5_5") (pintype "passive"))
    )
    (net (code "74") (name "unconnected-(J2-Pad6)") (class "Default")
      (node (ref "J2") (pin "6") (pinfunction "6_6") (pintype "passive"))
    )
    (net (code "75") (name "unconnected-(J2-Pad7)") (class "Default")
      (node (ref "J2") (pin "7") (pinfunction "7_7") (pintype "passive"))
    )
    (net (code "76") (name "unconnected-(J2-Pad8)") (class "Default")
      (node (ref "J2") (pin "8") (pinfunction "8_8") (pintype "passive"))
    )
    (net (code "77") (name "unconnected-(J2-Pad9)") (class "Default")
      (node (ref "J2") (pin "9") (pinfunction "9_9") (pintype "passive"))
    )
    (net (code "78") (name "unconnected-(J2-Pad10)") (class "Default")
      (node (ref "J2") (pin "10") (pinfunction "10_10") (pintype "passive"))
    )
    (net (code "79") (name "unconnected-(J3-Pad1)") (class "Default")
      (node (ref "J3") (pin "1") (pinfunction "1_1") (pintype "passive"))
    )
    (net (code "80") (name "unconnected-(J3-Pad2)") (class "Default")
      (node (ref "J3") (pin "2") (pinfunction "2_2") (pintype "passive"))
    )
    (net (code "81") (name "unconnected-(J3-Pad3)") (class "Default")
      (node (ref "J3") (pin "3") (pinfunction "3_3") (pintype "passive"))
    )
    (net (code "82") (name "unconnected-(J3-Pad4)") (class "Default")
      (node (ref "J3") (pin "4") (pinfunction "4_4") (pintype "passive"))
    )
    (net (code "83") (name "unconnected-(J3-Pad5)") (class "Default")
      (node (ref "J3") (pin "5") (pinfunction "5_5") (pintype "passive"))
    )
    (net (code "84") (name "unconnected-(J3-Pad6)") (class "Default")
      (node (ref "J3") (pin "6") (pinfunction "6_6") (pintype "passive"))
    )
    (net (code "85") (name "unconnected-(J3-Pad7)") (class "Default")
      (node (ref "J3") (pin "7") (pinfunction "7_7") (pintype "passive"))
    )
    (net (code "86") (name "unconnected-(J3-Pad8)") (class "Default")
      (node (ref "J3") (pin "8") (pinfunction "8_8") (pintype "passive"))
    )
    (net (code "87") (name "unconnected-(J3-Pad9)") (class "Default")
      (node (ref "J3") (pin "9") (pinfunction "9_9") (pintype "passive"))
    )
    (net (code "88") (name "unconnected-(J3-Pad10)") (class "Default")
      (node (ref "J3") (pin "10") (pinfunction "10_10") (pintype "passive"))
    )
    (net (code "89") (name "unconnected-(J4-Pad1)") (class "Default")
      (node (ref "J4") (pin "1") (pinfunction "1_1") (pintype "passive"))
    )
    (net (code "90") (name "unconnected-(J4-Pad6)") (class "Default")
      (node (ref "J4") (pin "6") (pinfunction "6_6") (pintype "passive"))
    )
    (net (code "91") (name "unconnected-(J4-Pad7)") (class "Default")
      (node (ref "J4") (pin "7") (pinfunction "7_7") (pintype "passive"))
    )
    (net (code "92") (name "unconnected-(J4-Pad8)") (class "Default")
      (node (ref "J4") (pin "8") (pinfunction "8_8") (pintype "passive"))
    )
    (net (code "93") (name "unconnected-(J4-Pad9)") (class "Default")
      (node (ref "J4") (pin "9") (pinfunction "9_9") (pintype "passive"))
    )
    (net (code "94") (name "unconnected-(J4-Pad10)") (class "Default")
      (node (ref "J4") (pin "10") (pinfunction "10_10") (pintype "passive"))
    )
    (net (code "95") (name "unconnected-(J5-Pad1)") (class "Default")
      (node (ref "J5") (pin "1") (pinfunction "1_1") (pintype "passive"))
    )
    (net (code "96") (name "unconnected-(J6-Pad1)") (class "Default")
      (node (ref "J6") (pin "1") (pinfunction "1_1") (pintype "passive"))
    )
    (net (code "97") (name "unconnected-(J6-Pad2)") (class "Default")
      (node (ref "J6") (pin "2") (pinfunction "2_2") (pintype "passive"))
    )
    (net (code "98") (name "unconnected-(J6-Pad3)") (class "Default")
      (node (ref "J6") (pin "3") (pinfunction "3_3") (pintype "passive"))
    )
    (net (code "99") (name "unconnected-(J6-Pad4)") (class "Default")
      (node (ref "J6") (pin "4") (pinfunction "4_4") (pintype "passive"))
    )
    (net (code "100") (name "unconnected-(JP3-Pad1)") (class "Default")
      (node (ref "JP3") (pin "1") (pinfunction "1_1") (pintype "passive"))
    )
    (net (code "101") (name "unconnected-(JP4-Pad1)") (class "Default")
      (node (ref "JP4") (pin "1") (pinfunction "1_1") (pintype "passive"))
    )
  )
)
